# PI_SCH_FPC.net
KiCad netlist of a schematic drawn in EasyEDA
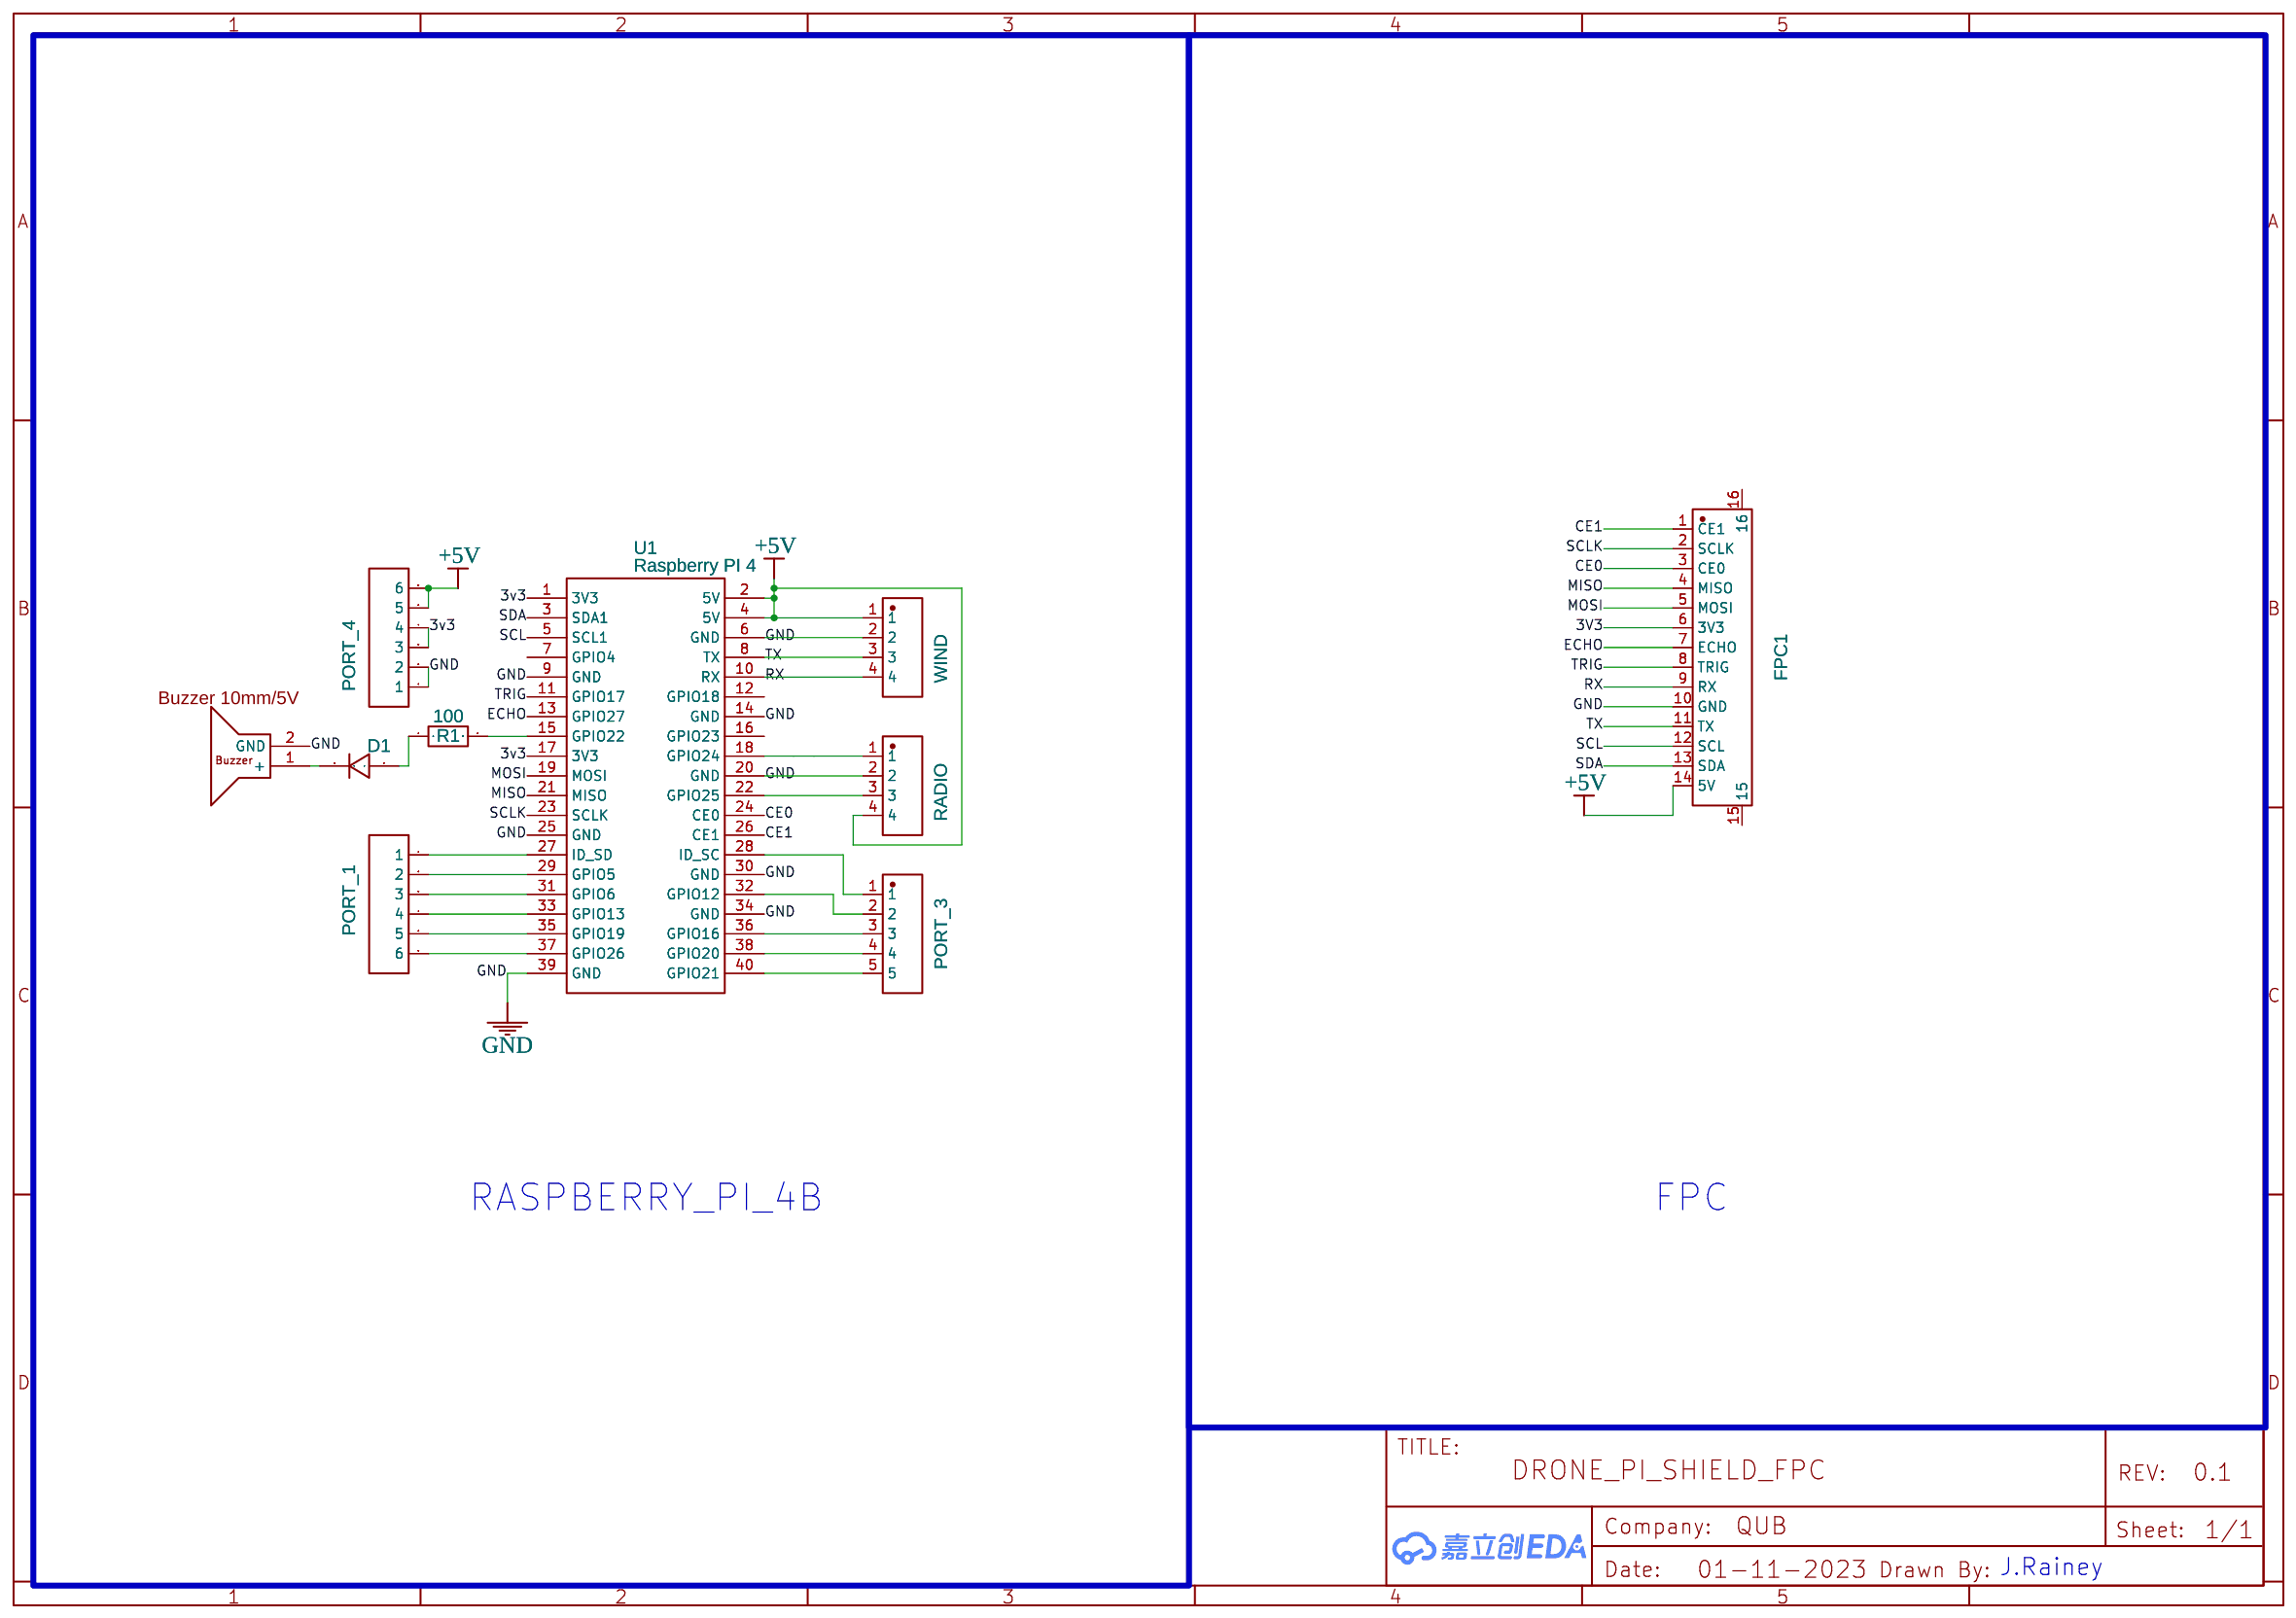
[diagram p0: schematic sheet]

(export (version "E")
  (design (tool "Eeschema 10.0.6"))
  (components
    (comp (ref "BUZZER1")
      (value "Buzzer 10mm/5V")
      (fields (field (name "BOM_Manufacturer Part") "BUZZER"))
      (libsource (lib "") (part "Buzzer 10mm/5V"))
    )
    (comp (ref "D1")
      (value "1N4448")
      (fields (field (name "Manufacturer") "ST(先科)"))
      (libsource (lib "") (part "1N4448"))
    )
    (comp (ref "FPC1")
      (value "1.0K-FX-14PWB")
      (fields (field (name "Manufacturer") "HDGC(华德共创)"))
      (libsource (lib "") (part "1.0K-FX-14PWB"))
    )
    (comp (ref "PORT_1")
      (value "HEADER-MALE-2.54_1X6")
      (fields
        (field (name "BOM_Manufacturer Part") "Header-Male-2.54_1x6")
        (field (name "BOM_Supplier Part") "C37208")
      )
      (libsource (lib "") (part "HEADER-MALE-2.54_1X6"))
    )
    (comp (ref "PORT_3")
      (value "PZ254V-11-05P")
      (fields (field (name "BOM_Supplier Part") "C492404"))
      (libsource (lib "") (part "PZ254V-11-05P"))
    )
    (comp (ref "PORT_4")
      (value "HEADER-MALE-2.54_1X6")
      (fields
        (field (name "BOM_Manufacturer Part") "Header-Male-2.54_1x6")
        (field (name "BOM_Supplier Part") "C37208")
      )
      (libsource (lib "") (part "HEADER-MALE-2.54_1X6_1"))
    )
    (comp (ref "R1") (value "100") (libsource (lib "") (part "R_AXIAL-0.4_EU")))
    (comp (ref "RADIO")
      (value "PZ254V-11-04P")
      (fields (field (name "BOM_Supplier Part") "C492403"))
      (libsource (lib "") (part "PZ254V-11-04P_1"))
    )
    (comp (ref "U1") (value "Raspberry PI 4") (libsource (lib "") (part "Raspberry PI 4")))
    (comp (ref "WIND")
      (value "PZ254V-11-04P")
      (fields (field (name "BOM_Supplier Part") "C492403"))
      (libsource (lib "") (part "PZ254V-11-04P"))
    )
  )
  (nets
    (net (code "1") (name "+5V") (class "Default")
      (node (ref "FPC1") (pin "14") (pinfunction "5V_14") (pintype "unspecified"))
      (node (ref "PORT_4") (pin "5") (pinfunction "5_5") (pintype "input"))
      (node (ref "PORT_4") (pin "6") (pinfunction "6_6") (pintype "input"))
      (node (ref "RADIO") (pin "4") (pinfunction "4_4") (pintype "unspecified"))
      (node (ref "U1") (pin "2") (pinfunction "5V_2") (pintype "unspecified"))
      (node (ref "U1") (pin "4") (pinfunction "5V_4") (pintype "unspecified"))
      (node (ref "WIND") (pin "1") (pinfunction "1_1") (pintype "unspecified"))
    )
    (net (code "2") (name "/3V3") (class "Default")
      (node (ref "FPC1") (pin "6") (pinfunction "3V3_6") (pintype "unspecified"))
    )
    (net (code "3") (name "/3v3") (class "Default")
      (node (ref "PORT_4") (pin "3") (pinfunction "3_3") (pintype "input"))
      (node (ref "PORT_4") (pin "4") (pinfunction "4_4") (pintype "input"))
      (node (ref "U1") (pin "1") (pinfunction "3V3_1") (pintype "unspecified"))
      (node (ref "U1") (pin "17") (pinfunction "3V3_17") (pintype "unspecified"))
    )
    (net (code "4") (name "/CE0") (class "Default")
      (node (ref "FPC1") (pin "3") (pinfunction "CE0_3") (pintype "unspecified"))
      (node (ref "U1") (pin "24") (pinfunction "CE0_24") (pintype "unspecified"))
    )
    (net (code "5") (name "/CE1") (class "Default")
      (node (ref "FPC1") (pin "1") (pinfunction "CE1_1") (pintype "unspecified"))
      (node (ref "U1") (pin "26") (pinfunction "CE1_26") (pintype "unspecified"))
    )
    (net (code "6") (name "/ECHO") (class "Default")
      (node (ref "FPC1") (pin "7") (pinfunction "ECHO_7") (pintype "unspecified"))
      (node (ref "U1") (pin "13") (pinfunction "GPIO27_13") (pintype "unspecified"))
    )
    (net (code "7") (name "/MISO") (class "Default")
      (node (ref "FPC1") (pin "4") (pinfunction "MISO_4") (pintype "unspecified"))
      (node (ref "U1") (pin "21") (pinfunction "MISO_21") (pintype "unspecified"))
    )
    (net (code "8") (name "/MOSI") (class "Default")
      (node (ref "FPC1") (pin "5") (pinfunction "MOSI_5") (pintype "unspecified"))
      (node (ref "U1") (pin "19") (pinfunction "MOSI_19") (pintype "unspecified"))
    )
    (net (code "9") (name "/RX") (class "Default")
      (node (ref "FPC1") (pin "9") (pinfunction "RX_9") (pintype "unspecified"))
      (node (ref "U1") (pin "10") (pinfunction "RX_10") (pintype "unspecified"))
      (node (ref "WIND") (pin "4") (pinfunction "4_4") (pintype "unspecified"))
    )
    (net (code "10") (name "/SCL") (class "Default")
      (node (ref "FPC1") (pin "12") (pinfunction "SCL_12") (pintype "unspecified"))
      (node (ref "U1") (pin "5") (pinfunction "SCL1_5") (pintype "unspecified"))
    )
    (net (code "11") (name "/SCLK") (class "Default")
      (node (ref "FPC1") (pin "2") (pinfunction "SCLK_2") (pintype "unspecified"))
      (node (ref "U1") (pin "23") (pinfunction "SCLK_23") (pintype "unspecified"))
    )
    (net (code "12") (name "/SDA") (class "Default")
      (node (ref "FPC1") (pin "13") (pinfunction "SDA_13") (pintype "unspecified"))
      (node (ref "U1") (pin "3") (pinfunction "SDA1_3") (pintype "unspecified"))
    )
    (net (code "13") (name "/TRIG") (class "Default")
      (node (ref "FPC1") (pin "8") (pinfunction "TRIG_8") (pintype "unspecified"))
      (node (ref "U1") (pin "11") (pinfunction "GPIO17_11") (pintype "unspecified"))
    )
    (net (code "14") (name "/TX") (class "Default")
      (node (ref "FPC1") (pin "11") (pinfunction "TX_11") (pintype "unspecified"))
      (node (ref "U1") (pin "8") (pinfunction "TX_8") (pintype "unspecified"))
      (node (ref "WIND") (pin "3") (pinfunction "3_3") (pintype "unspecified"))
    )
    (net (code "15") (name "GND") (class "Default")
      (node (ref "BUZZER1") (pin "2") (pinfunction "GND_2") (pintype "unspecified"))
      (node (ref "FPC1") (pin "10") (pinfunction "GND_10") (pintype "unspecified"))
      (node (ref "PORT_4") (pin "1") (pinfunction "1_1") (pintype "input"))
      (node (ref "PORT_4") (pin "2") (pinfunction "2_2") (pintype "input"))
      (node (ref "RADIO") (pin "2") (pinfunction "2_2") (pintype "unspecified"))
      (node (ref "U1") (pin "14") (pinfunction "GND_14") (pintype "unspecified"))
      (node (ref "U1") (pin "20") (pinfunction "GND_20") (pintype "unspecified"))
      (node (ref "U1") (pin "25") (pinfunction "GND_25") (pintype "unspecified"))
      (node (ref "U1") (pin "30") (pinfunction "GND_30") (pintype "unspecified"))
      (node (ref "U1") (pin "34") (pinfunction "GND_34") (pintype "unspecified"))
      (node (ref "U1") (pin "39") (pinfunction "GND_39") (pintype "unspecified"))
      (node (ref "U1") (pin "6") (pinfunction "GND_6") (pintype "unspecified"))
      (node (ref "U1") (pin "9") (pinfunction "GND_9") (pintype "unspecified"))
      (node (ref "WIND") (pin "2") (pinfunction "2_2") (pintype "unspecified"))
    )
    (net (code "16") (name "Net-(BUZZER1-+)") (class "Default")
      (node (ref "BUZZER1") (pin "1") (pinfunction "+_1") (pintype "unspecified"))
      (node (ref "D1") (pin "2") (pinfunction "K_2") (pintype "unspecified"))
    )
    (net (code "17") (name "Net-(D1-A)") (class "Default")
      (node (ref "D1") (pin "1") (pinfunction "A_1") (pintype "unspecified"))
      (node (ref "R1") (pin "1") (pinfunction "1_1") (pintype "unspecified"))
    )
    (net (code "18") (name "Net-(U1-GPIO5)") (class "Default")
      (node (ref "PORT_1") (pin "2") (pinfunction "2_2") (pintype "input"))
      (node (ref "U1") (pin "29") (pinfunction "GPIO5_29") (pintype "unspecified"))
    )
    (net (code "19") (name "Net-(U1-GPIO6)") (class "Default")
      (node (ref "PORT_1") (pin "3") (pinfunction "3_3") (pintype "input"))
      (node (ref "U1") (pin "31") (pinfunction "GPIO6_31") (pintype "unspecified"))
    )
    (net (code "20") (name "Net-(U1-GPIO12)") (class "Default")
      (node (ref "PORT_3") (pin "2") (pinfunction "2_2") (pintype "unspecified"))
      (node (ref "U1") (pin "32") (pinfunction "GPIO12_32") (pintype "unspecified"))
    )
    (net (code "21") (name "Net-(U1-GPIO13)") (class "Default")
      (node (ref "PORT_1") (pin "4") (pinfunction "4_4") (pintype "input"))
      (node (ref "U1") (pin "33") (pinfunction "GPIO13_33") (pintype "unspecified"))
    )
    (net (code "22") (name "Net-(U1-GPIO16)") (class "Default")
      (node (ref "PORT_3") (pin "3") (pinfunction "3_3") (pintype "unspecified"))
      (node (ref "U1") (pin "36") (pinfunction "GPIO16_36") (pintype "unspecified"))
    )
    (net (code "23") (name "Net-(U1-GPIO19)") (class "Default")
      (node (ref "PORT_1") (pin "5") (pinfunction "5_5") (pintype "input"))
      (node (ref "U1") (pin "35") (pinfunction "GPIO19_35") (pintype "unspecified"))
    )
    (net (code "24") (name "Net-(U1-GPIO20)") (class "Default")
      (node (ref "PORT_3") (pin "4") (pinfunction "4_4") (pintype "unspecified"))
      (node (ref "U1") (pin "38") (pinfunction "GPIO20_38") (pintype "unspecified"))
    )
    (net (code "25") (name "Net-(U1-GPIO21)") (class "Default")
      (node (ref "PORT_3") (pin "5") (pinfunction "5_5") (pintype "unspecified"))
      (node (ref "U1") (pin "40") (pinfunction "GPIO21_40") (pintype "unspecified"))
    )
    (net (code "26") (name "Net-(U1-GPIO22)") (class "Default")
      (node (ref "R1") (pin "2") (pinfunction "2_2") (pintype "unspecified"))
      (node (ref "U1") (pin "15") (pinfunction "GPIO22_15") (pintype "unspecified"))
    )
    (net (code "27") (name "Net-(U1-GPIO24)") (class "Default")
      (node (ref "RADIO") (pin "1") (pinfunction "1_1") (pintype "unspecified"))
      (node (ref "U1") (pin "18") (pinfunction "GPIO24_18") (pintype "unspecified"))
    )
    (net (code "28") (name "Net-(U1-GPIO25)") (class "Default")
      (node (ref "RADIO") (pin "3") (pinfunction "3_3") (pintype "unspecified"))
      (node (ref "U1") (pin "22") (pinfunction "GPIO25_22") (pintype "unspecified"))
    )
    (net (code "29") (name "Net-(U1-GPIO26)") (class "Default")
      (node (ref "PORT_1") (pin "6") (pinfunction "6_6") (pintype "input"))
      (node (ref "U1") (pin "37") (pinfunction "GPIO26_37") (pintype "unspecified"))
    )
    (net (code "30") (name "Net-(U1-ID_SC)") (class "Default")
      (node (ref "PORT_3") (pin "1") (pinfunction "1_1") (pintype "unspecified"))
      (node (ref "U1") (pin "28") (pinfunction "ID_SC_28") (pintype "unspecified"))
    )
    (net (code "31") (name "Net-(U1-ID_SD)") (class "Default")
      (node (ref "PORT_1") (pin "1") (pinfunction "1_1") (pintype "input"))
      (node (ref "U1") (pin "27") (pinfunction "ID_SD_27") (pintype "unspecified"))
    )
    (net (code "32") (name "unconnected-(FPC1-Pad15)") (class "Default")
      (node (ref "FPC1") (pin "15") (pinfunction "15_15") (pintype "unspecified"))
    )
    (net (code "33") (name "unconnected-(FPC1-Pad16)") (class "Default")
      (node (ref "FPC1") (pin "16") (pinfunction "16_16") (pintype "unspecified"))
    )
    (net (code "34") (name "unconnected-(U1-GPIO4-Pad7)") (class "Default")
      (node (ref "U1") (pin "7") (pinfunction "GPIO4_7") (pintype "unspecified"))
    )
    (net (code "35") (name "unconnected-(U1-GPIO18-Pad12)") (class "Default")
      (node (ref "U1") (pin "12") (pinfunction "GPIO18_12") (pintype "unspecified"))
    )
    (net (code "36") (name "unconnected-(U1-GPIO23-Pad16)") (class "Default")
      (node (ref "U1") (pin "16") (pinfunction "GPIO23_16") (pintype "unspecified"))
    )
  )
)
